# WdTest.net
KiCad netlist of a schematic drawn in Altium Designer
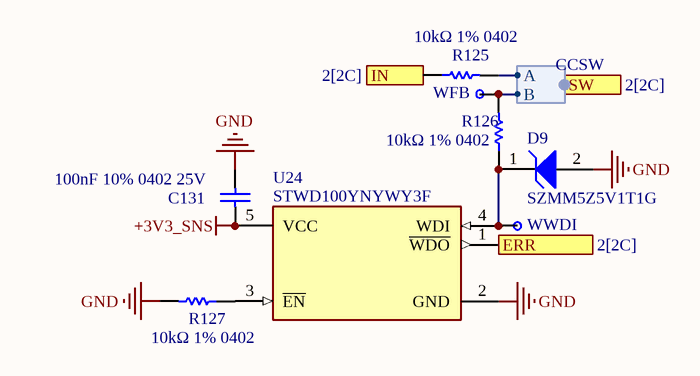
[diagram p0: WdTest.SchDoc]

(export (version "E")
  (design (tool "Eeschema 10.0.6"))
  (components
    (comp (ref "C131")
      (value "100nF 10% 0402 25V")
      (footprint "0402N")
      (fields (field (name "TOLERANCE") "10") (field (name "VOLTAGE") "25"))
      (libsource (lib "MiscPassives") (part "C0402"))
    )
    (comp (ref "D9")
      (value "SZMM5Z5V1T1G")
      (footprint "ONSC-SOD-523-2-502-01_V")
      (description "Zener Voltage Regulator, 500 mW, 2-Pin SOD-523, Pb-Free, Tape and Reel")
      (fields (field (name "MANUFACTURER") "On Semiconductor"))
      (libsource (lib "Altium Content Vault") (part "ONSC-K1A2-2"))
    )
    (comp (ref "R125")
      (value "10kΩ 1% 0402")
      (footprint "0402N")
      (fields (field (name "TOLERANCE") "1"))
      (libsource (lib "MiscPassives") (part "R0402"))
    )
    (comp (ref "R126")
      (value "10kΩ 1% 0402")
      (footprint "0402N")
      (fields (field (name "TOLERANCE") "1"))
      (libsource (lib "MiscPassives") (part "R0402"))
    )
    (comp (ref "R127")
      (value "10kΩ 1% 0402")
      (footprint "0402N")
      (fields (field (name "TOLERANCE") "1"))
      (libsource (lib "MiscPassives") (part "R0402"))
    )
    (comp (ref "U24")
      (value "STWD100YNYWY3F")
      (footprint "FP-SOT23-5-IPC_B")
      (description "IC SUPERVISOR 1 CHANNEL SOT23-5")
      (libsource (lib "Altium Content Vault") (part "4430cfcf905b8782080de0ac9be49f1"))
    )
    (comp (ref "WFB")
      (value "Testpoint")
      (footprint "Testpoint-Footprint-1")
      (libsource (lib "Saule S.A") (part "Testpoint"))
    )
    (comp (ref "WWDI")
      (value "Testpoint")
      (footprint "Testpoint-Footprint-1")
      (libsource (lib "Saule S.A") (part "Testpoint"))
    )
  )
  (nets
    (net (code "2") (name "+3V3_SNS") (class "Default")
      (node (ref "C131") (pin "1") (pinfunction "1_1") (pintype "passive"))
      (node (ref "U24") (pin "5") (pinfunction "VCC_5") (pintype "power_in"))
    )
    (net (code "3") (name "/A") (class "Default")
      (node (ref "R125") (pin "2") (pinfunction "2_2") (pintype "passive"))
    )
    (net (code "4") (name "/B") (class "Default")
      (node (ref "R126") (pin "2") (pinfunction "2_2") (pintype "passive"))
      (node (ref "WFB") (pin "1") (pinfunction "1_1") (pintype "passive"))
    )
    (net (code "5") (name "/ERR") (class "Default")
      (node (ref "U24") (pin "1") (pinfunction "~{WDO}_1") (pintype "output"))
    )
    (net (code "6") (name "/IN") (class "Default")
      (node (ref "R125") (pin "1") (pinfunction "1_1") (pintype "passive"))
    )
    (net (code "8") (name "GND") (class "Default")
      (node (ref "C131") (pin "2") (pinfunction "2_2") (pintype "passive"))
      (node (ref "D9") (pin "2") (pinfunction "A_2") (pintype "passive"))
      (node (ref "R127") (pin "2") (pinfunction "2_2") (pintype "passive"))
      (node (ref "U24") (pin "2") (pinfunction "GND_2") (pintype "power_in"))
    )
    (net (code "9") (name "Net-(D9-K)") (class "Default")
      (node (ref "D9") (pin "1") (pinfunction "K_1") (pintype "passive"))
      (node (ref "R126") (pin "1") (pinfunction "1_1") (pintype "passive"))
      (node (ref "U24") (pin "4") (pinfunction "WDI_4") (pintype "input"))
      (node (ref "WWDI") (pin "1") (pinfunction "1_1") (pintype "passive"))
    )
    (net (code "10") (name "Net-(U24-~{EN})") (class "Default")
      (node (ref "R127") (pin "1") (pinfunction "1_1") (pintype "passive"))
      (node (ref "U24") (pin "3") (pinfunction "~{EN}_3") (pintype "input"))
    )
  )
)
